# MODI.net
KiCad netlist of a schematic drawn in EAGLE
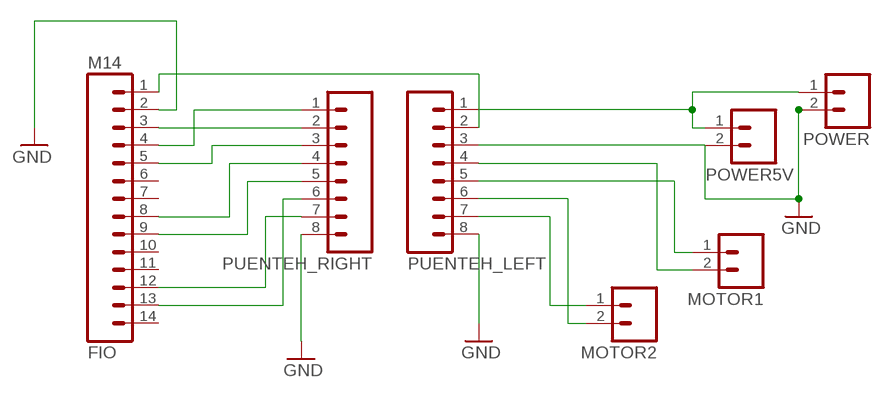
[diagram p0: schematic, sheet 1]

(export (version "E")
  (design (tool "Eeschema 10.0.6"))
  (components
    (comp (ref "FIO")
      (value "M14")
      (footprint "eagle-import:1X14")
      (libsource (lib "eagle-import") (part "M14"))
    )
    (comp (ref "MOTOR1")
      (value "M023.5MM")
      (footprint "eagle-import:SCREWTERMINAL-3.5MM-2")
      (libsource (lib "eagle-import") (part "M023.5MM"))
    )
    (comp (ref "MOTOR2")
      (value "M023.5MM")
      (footprint "eagle-import:SCREWTERMINAL-3.5MM-2")
      (libsource (lib "eagle-import") (part "M023.5MM"))
    )
    (comp (ref "POWER")
      (value "M023.5MM")
      (footprint "eagle-import:SCREWTERMINAL-3.5MM-2")
      (libsource (lib "eagle-import") (part "M023.5MM"))
    )
    (comp (ref "POWER5V")
      (value "M02PTH")
      (footprint "eagle-import:1X02")
      (libsource (lib "eagle-import") (part "M02PTH"))
    )
    (comp (ref "PUENTEH_LEFT")
      (value "M08LONGPADS")
      (footprint "eagle-import:1X08_LONGPADS")
      (libsource (lib "eagle-import") (part "M08LONGPADS"))
    )
    (comp (ref "PUENTEH_RIGHT")
      (value "M08LONGPADS")
      (footprint "eagle-import:1X08_LONGPADS")
      (libsource (lib "eagle-import") (part "M08LONGPADS"))
    )
  )
  (nets
    (net (code "1") (name "GND") (class "Default")
      (node (ref "FIO") (pin "2") (pinfunction "2_2") (pintype "passive"))
      (node (ref "POWER") (pin "2") (pinfunction "2_2") (pintype "passive"))
      (node (ref "POWER5V") (pin "2") (pinfunction "2_2") (pintype "passive"))
      (node (ref "PUENTEH_LEFT") (pin "3") (pinfunction "3_3") (pintype "passive"))
      (node (ref "PUENTEH_LEFT") (pin "8") (pinfunction "8_8") (pintype "passive"))
      (node (ref "PUENTEH_RIGHT") (pin "8") (pinfunction "8_8") (pintype "passive"))
    )
    (net (code "2") (name "Net-(FIO-Pad1)") (class "Default")
      (node (ref "FIO") (pin "1") (pinfunction "1_1") (pintype "passive"))
      (node (ref "PUENTEH_LEFT") (pin "2") (pinfunction "2_2") (pintype "passive"))
    )
    (net (code "3") (name "Net-(FIO-Pad3)") (class "Default")
      (node (ref "FIO") (pin "3") (pinfunction "3_3") (pintype "passive"))
      (node (ref "PUENTEH_RIGHT") (pin "2") (pinfunction "2_2") (pintype "passive"))
    )
    (net (code "4") (name "Net-(FIO-Pad4)") (class "Default")
      (node (ref "FIO") (pin "4") (pinfunction "4_4") (pintype "passive"))
      (node (ref "PUENTEH_RIGHT") (pin "1") (pinfunction "1_1") (pintype "passive"))
    )
    (net (code "5") (name "Net-(FIO-Pad5)") (class "Default")
      (node (ref "FIO") (pin "5") (pinfunction "5_5") (pintype "passive"))
      (node (ref "PUENTEH_RIGHT") (pin "3") (pinfunction "3_3") (pintype "passive"))
    )
    (net (code "6") (name "Net-(FIO-Pad8)") (class "Default")
      (node (ref "FIO") (pin "8") (pinfunction "8_8") (pintype "passive"))
      (node (ref "PUENTEH_RIGHT") (pin "4") (pinfunction "4_4") (pintype "passive"))
    )
    (net (code "7") (name "Net-(FIO-Pad9)") (class "Default")
      (node (ref "FIO") (pin "9") (pinfunction "9_9") (pintype "passive"))
      (node (ref "PUENTEH_RIGHT") (pin "5") (pinfunction "5_5") (pintype "passive"))
    )
    (net (code "8") (name "Net-(FIO-Pad12)") (class "Default")
      (node (ref "FIO") (pin "12") (pinfunction "12_12") (pintype "passive"))
      (node (ref "PUENTEH_RIGHT") (pin "7") (pinfunction "7_7") (pintype "passive"))
    )
    (net (code "9") (name "Net-(FIO-Pad13)") (class "Default")
      (node (ref "FIO") (pin "13") (pinfunction "13_13") (pintype "passive"))
      (node (ref "PUENTEH_RIGHT") (pin "6") (pinfunction "6_6") (pintype "passive"))
    )
    (net (code "10") (name "Net-(MOTOR1-Pad1)") (class "Default")
      (node (ref "MOTOR1") (pin "1") (pinfunction "1_1") (pintype "passive"))
      (node (ref "PUENTEH_LEFT") (pin "5") (pinfunction "5_5") (pintype "passive"))
    )
    (net (code "11") (name "Net-(MOTOR1-Pad2)") (class "Default")
      (node (ref "MOTOR1") (pin "2") (pinfunction "2_2") (pintype "passive"))
      (node (ref "PUENTEH_LEFT") (pin "4") (pinfunction "4_4") (pintype "passive"))
    )
    (net (code "12") (name "Net-(MOTOR2-Pad1)") (class "Default")
      (node (ref "MOTOR2") (pin "1") (pinfunction "1_1") (pintype "passive"))
      (node (ref "PUENTEH_LEFT") (pin "7") (pinfunction "7_7") (pintype "passive"))
    )
    (net (code "13") (name "Net-(MOTOR2-Pad2)") (class "Default")
      (node (ref "MOTOR2") (pin "2") (pinfunction "2_2") (pintype "passive"))
      (node (ref "PUENTEH_LEFT") (pin "6") (pinfunction "6_6") (pintype "passive"))
    )
    (net (code "14") (name "Net-(POWER-Pad1)") (class "Default")
      (node (ref "POWER") (pin "1") (pinfunction "1_1") (pintype "passive"))
      (node (ref "POWER5V") (pin "1") (pinfunction "1_1") (pintype "passive"))
      (node (ref "PUENTEH_LEFT") (pin "1") (pinfunction "1_1") (pintype "passive"))
    )
    (net (code "15") (name "unconnected-(FIO-Pad6)") (class "Default")
      (node (ref "FIO") (pin "6") (pinfunction "6_6") (pintype "passive"))
    )
    (net (code "16") (name "unconnected-(FIO-Pad7)") (class "Default")
      (node (ref "FIO") (pin "7") (pinfunction "7_7") (pintype "passive"))
    )
    (net (code "17") (name "unconnected-(FIO-Pad10)") (class "Default")
      (node (ref "FIO") (pin "10") (pinfunction "10_10") (pintype "passive"))
    )
    (net (code "18") (name "unconnected-(FIO-Pad11)") (class "Default")
      (node (ref "FIO") (pin "11") (pinfunction "11_11") (pintype "passive"))
    )
    (net (code "19") (name "unconnected-(FIO-Pad14)") (class "Default")
      (node (ref "FIO") (pin "14") (pinfunction "14_14") (pintype "passive"))
    )
  )
)
